# ECG_circuit.net
KiCad netlist of a schematic drawn in Altium Designer
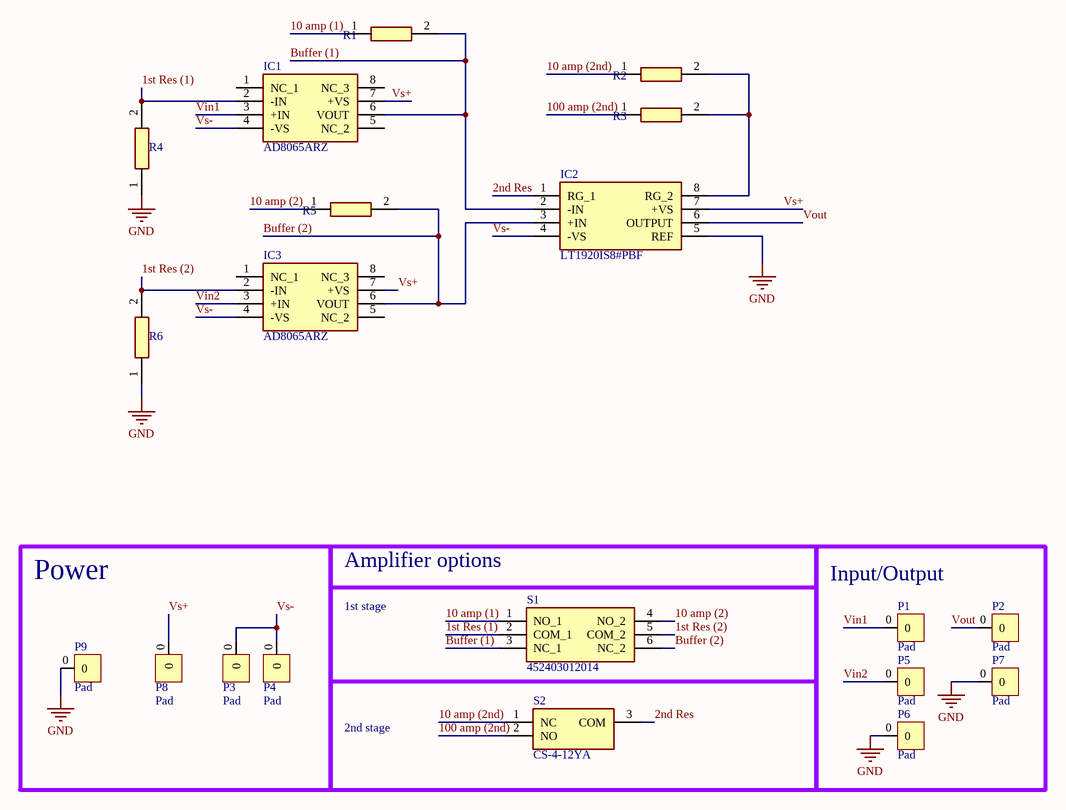
[diagram p0: ECG circuit.SchDoc]

(export (version "E")
  (design (tool "Eeschema 10.0.6"))
  (components
    (comp (ref "IC1")
      (value "AD8065ARZ")
      (footprint "SamacSys:SOIC127P600X175-8N")
      (description "Integrated Circuit")
      (fields (field (name "MOUSER PART NUMBER") "584-AD8065ARZ"))
      (libsource (lib "SamacSys") (part "AD8065ARZ"))
    )
    (comp (ref "IC2")
      (value "LT1920IS8#PBF")
      (footprint "SamacSys:SOIC127P599X175-8N")
      (description "Integrated Circuit")
      (fields (field (name "MOUSER PART NUMBER") "584-LT1920IS8#PBF"))
      (libsource (lib "SamacSys") (part "LT1920IS8#PBF"))
    )
    (comp (ref "IC3")
      (value "AD8065ARZ")
      (footprint "SamacSys:SOIC127P600X175-8N")
      (description "Integrated Circuit")
      (fields (field (name "MOUSER PART NUMBER") "584-AD8065ARZ"))
      (libsource (lib "SamacSys") (part "AD8065ARZ"))
    )
    (comp (ref "P1") (value "Pad") (footprint "Pad") (libsource (lib "") (part "Pad_1")))
    (comp (ref "P2") (value "Pad") (footprint "Pad") (libsource (lib "") (part "Pad_1")))
    (comp (ref "P3") (value "Pad") (footprint "Pad") (libsource (lib "SamacSys") (part "Pad")))
    (comp (ref "P4") (value "Pad") (footprint "Pad") (libsource (lib "SamacSys") (part "Pad")))
    (comp (ref "P5") (value "Pad") (footprint "Pad") (libsource (lib "") (part "Pad_1")))
    (comp (ref "P6") (value "Pad") (footprint "Pad") (libsource (lib "") (part "Pad_1")))
    (comp (ref "P7") (value "Pad") (footprint "Pad") (libsource (lib "") (part "Pad_1")))
    (comp (ref "P8") (value "Pad") (footprint "Pad") (libsource (lib "SamacSys") (part "Pad")))
    (comp (ref "P9") (value "Pad") (footprint "Pad") (libsource (lib "") (part "Pad_1")))
    (comp (ref "R1")
      (value "CRF0805-FZ-R002ELF")
      (footprint "SamacSys:RESC2012X80N")
      (description "Resistor")
      (fields (field (name "MOUSER PART NUMBER") "652-CRF0805FZR002ELF"))
      (libsource (lib "SamacSys") (part "CRF0805-FZ-R002ELF"))
    )
    (comp (ref "R2")
      (value "CRF0805-FZ-R002ELF")
      (footprint "SamacSys:RESC2012X80N")
      (description "Resistor")
      (fields (field (name "MOUSER PART NUMBER") "652-CRF0805FZR002ELF"))
      (libsource (lib "SamacSys") (part "CRF0805-FZ-R002ELF"))
    )
    (comp (ref "R3")
      (value "CRF0805-FZ-R002ELF")
      (footprint "SamacSys:RESC2012X80N")
      (description "Resistor")
      (fields (field (name "MOUSER PART NUMBER") "652-CRF0805FZR002ELF"))
      (libsource (lib "SamacSys") (part "CRF0805-FZ-R002ELF"))
    )
    (comp (ref "R4")
      (value "CRF0805-FZ-R002ELF")
      (footprint "SamacSys:RESC2012X80N")
      (description "Resistor")
      (fields (field (name "MOUSER PART NUMBER") "652-CRF0805FZR002ELF"))
      (libsource (lib "") (part "CRF0805-FZ-R002ELF_1"))
    )
    (comp (ref "R5")
      (value "CRF0805-FZ-R002ELF")
      (footprint "SamacSys:RESC2012X80N")
      (description "Resistor")
      (fields (field (name "MOUSER PART NUMBER") "652-CRF0805FZR002ELF"))
      (libsource (lib "SamacSys") (part "CRF0805-FZ-R002ELF"))
    )
    (comp (ref "R6")
      (value "CRF0805-FZ-R002ELF")
      (footprint "SamacSys:RESC2012X80N")
      (description "Resistor")
      (fields (field (name "MOUSER PART NUMBER") "652-CRF0805FZR002ELF"))
      (libsource (lib "") (part "CRF0805-FZ-R002ELF_1"))
    )
    (comp (ref "S1")
      (value "452403012014")
      (footprint "SamacSys:452403012014")
      (description "Switch")
      (fields (field (name "MOUSER PART NUMBER") "710-452403012014"))
      (libsource (lib "SamacSys") (part "452403012014"))
    )
    (comp (ref "S2")
      (value "CS-4-12YA")
      (footprint "SamacSys:CS412YA")
      (description "Switch")
      (libsource (lib "SamacSys") (part "CS-4-12YA"))
    )
  )
  (nets
    (net (code "1") (name "/1st Res (1)") (class "Default")
      (node (ref "IC1") (pin "2") (pinfunction "-IN_2") (pintype "passive"))
      (node (ref "R4") (pin "2") (pinfunction "2_2") (pintype "passive"))
      (node (ref "S1") (pin "2") (pinfunction "COM_1_2") (pintype "passive"))
    )
    (net (code "2") (name "/1st Res (2)") (class "Default")
      (node (ref "IC3") (pin "2") (pinfunction "-IN_2") (pintype "passive"))
      (node (ref "R6") (pin "2") (pinfunction "2_2") (pintype "passive"))
      (node (ref "S1") (pin "5") (pinfunction "COM_2_5") (pintype "passive"))
    )
    (net (code "3") (name "/2nd Res") (class "Default")
      (node (ref "IC2") (pin "1") (pinfunction "RG_1_1") (pintype "passive"))
      (node (ref "S2") (pin "3") (pinfunction "COM_3") (pintype "passive"))
    )
    (net (code "4") (name "/10 amp (1)") (class "Default")
      (node (ref "R1") (pin "1") (pinfunction "1_1") (pintype "passive"))
      (node (ref "S1") (pin "1") (pinfunction "NO_1_1") (pintype "passive"))
    )
    (net (code "5") (name "/10 amp (2)") (class "Default")
      (node (ref "R5") (pin "1") (pinfunction "1_1") (pintype "passive"))
      (node (ref "S1") (pin "4") (pinfunction "NO_2_4") (pintype "passive"))
    )
    (net (code "6") (name "/10 amp (2nd)") (class "Default")
      (node (ref "R2") (pin "1") (pinfunction "1_1") (pintype "passive"))
      (node (ref "S2") (pin "1") (pinfunction "NC_1") (pintype "passive"))
    )
    (net (code "7") (name "/100 amp (2nd)") (class "Default")
      (node (ref "R3") (pin "1") (pinfunction "1_1") (pintype "passive"))
      (node (ref "S2") (pin "2") (pinfunction "NO_2") (pintype "passive"))
    )
    (net (code "8") (name "/Buffer (1)") (class "Default")
      (node (ref "IC1") (pin "6") (pinfunction "VOUT_6") (pintype "passive"))
      (node (ref "IC2") (pin "2") (pinfunction "-IN_2") (pintype "passive"))
      (node (ref "R1") (pin "2") (pinfunction "2_2") (pintype "passive"))
      (node (ref "S1") (pin "3") (pinfunction "NC_1_3") (pintype "passive"))
    )
    (net (code "9") (name "/Buffer (2)") (class "Default")
      (node (ref "IC2") (pin "3") (pinfunction "+IN_3") (pintype "passive"))
      (node (ref "IC3") (pin "6") (pinfunction "VOUT_6") (pintype "passive"))
      (node (ref "R5") (pin "2") (pinfunction "2_2") (pintype "passive"))
      (node (ref "S1") (pin "6") (pinfunction "NC_2_6") (pintype "passive"))
    )
    (net (code "10") (name "/Vin1") (class "Default")
      (node (ref "IC1") (pin "3") (pinfunction "+IN_3") (pintype "passive"))
      (node (ref "P1") (pin "0") (pinfunction "0_0") (pintype "passive"))
    )
    (net (code "11") (name "/Vin2") (class "Default")
      (node (ref "IC3") (pin "3") (pinfunction "+IN_3") (pintype "passive"))
      (node (ref "P5") (pin "0") (pinfunction "0_0") (pintype "passive"))
    )
    (net (code "12") (name "/Vout") (class "Default")
      (node (ref "IC2") (pin "6") (pinfunction "OUTPUT_6") (pintype "passive"))
      (node (ref "P2") (pin "0") (pinfunction "0_0") (pintype "passive"))
    )
    (net (code "13") (name "/Vs+") (class "Default")
      (node (ref "IC1") (pin "7") (pinfunction "+VS_7") (pintype "passive"))
      (node (ref "IC2") (pin "7") (pinfunction "+VS_7") (pintype "passive"))
      (node (ref "IC3") (pin "7") (pinfunction "+VS_7") (pintype "passive"))
      (node (ref "P8") (pin "0") (pinfunction "0_0") (pintype "passive"))
    )
    (net (code "14") (name "/Vs-") (class "Default")
      (node (ref "IC1") (pin "4") (pinfunction "-VS_4") (pintype "passive"))
      (node (ref "IC2") (pin "4") (pinfunction "-VS_4") (pintype "passive"))
      (node (ref "IC3") (pin "4") (pinfunction "-VS_4") (pintype "passive"))
      (node (ref "P3") (pin "0") (pinfunction "0_0") (pintype "passive"))
      (node (ref "P4") (pin "0") (pinfunction "0_0") (pintype "passive"))
    )
    (net (code "15") (name "GND") (class "Default")
      (node (ref "IC2") (pin "5") (pinfunction "REF_5") (pintype "passive"))
      (node (ref "P6") (pin "0") (pinfunction "0_0") (pintype "passive"))
      (node (ref "P7") (pin "0") (pinfunction "0_0") (pintype "passive"))
      (node (ref "P9") (pin "0") (pinfunction "0_0") (pintype "passive"))
      (node (ref "R4") (pin "1") (pinfunction "1_1") (pintype "passive"))
      (node (ref "R6") (pin "1") (pinfunction "1_1") (pintype "passive"))
    )
    (net (code "16") (name "Net-(IC2-RG_2)") (class "Default")
      (node (ref "IC2") (pin "8") (pinfunction "RG_2_8") (pintype "passive"))
      (node (ref "R2") (pin "2") (pinfunction "2_2") (pintype "passive"))
      (node (ref "R3") (pin "2") (pinfunction "2_2") (pintype "passive"))
    )
    (net (code "17") (name "unconnected-(IC1-NC_1-Pad1)") (class "Default")
      (node (ref "IC1") (pin "1") (pinfunction "NC_1_1") (pintype "passive"))
    )
    (net (code "18") (name "unconnected-(IC1-NC_2-Pad5)") (class "Default")
      (node (ref "IC1") (pin "5") (pinfunction "NC_2_5") (pintype "passive"))
    )
    (net (code "19") (name "unconnected-(IC1-NC_3-Pad8)") (class "Default")
      (node (ref "IC1") (pin "8") (pinfunction "NC_3_8") (pintype "passive"))
    )
    (net (code "20") (name "unconnected-(IC3-NC_1-Pad1)") (class "Default")
      (node (ref "IC3") (pin "1") (pinfunction "NC_1_1") (pintype "passive"))
    )
    (net (code "21") (name "unconnected-(IC3-NC_2-Pad5)") (class "Default")
      (node (ref "IC3") (pin "5") (pinfunction "NC_2_5") (pintype "passive"))
    )
    (net (code "22") (name "unconnected-(IC3-NC_3-Pad8)") (class "Default")
      (node (ref "IC3") (pin "8") (pinfunction "NC_3_8") (pintype "passive"))
    )
  )
)
